# ColumnDriver.net
KiCad netlist of a schematic drawn in EAGLE
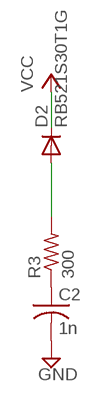
[diagram p0: schematic, sheet 1]

(export (version "E")
  (design (tool "Eeschema 10.0.6"))
  (components
    (comp (ref "C2")
      (value "1n")
      (footprint "eagle-import:C0805")
      (libsource (lib "eagle-import") (part "C-USC0805"))
    )
    (comp (ref "D2")
      (value "RB521S30T1G")
      (footprint "eagle-import:SOD523")
      (libsource (lib "eagle-import") (part "DIODE-SOD523"))
    )
    (comp (ref "R3")
      (value "300")
      (footprint "eagle-import:R0805")
      (libsource (lib "eagle-import") (part "R-US_R0805"))
    )
  )
  (nets
    (net (code "1") (name "GND") (class "Default")
      (node (ref "C2") (pin "2") (pinfunction "2_2") (pintype "passive"))
    )
    (net (code "2") (name "Net-(C2-Pad1)") (class "Default")
      (node (ref "C2") (pin "1") (pinfunction "1_1") (pintype "passive"))
      (node (ref "R3") (pin "1") (pinfunction "1_1") (pintype "passive"))
    )
    (net (code "3") (name "Net-(D2-PadA)") (class "Default")
      (node (ref "D2") (pin "A") (pinfunction "A_A") (pintype "passive"))
      (node (ref "R3") (pin "2") (pinfunction "2_2") (pintype "passive"))
    )
    (net (code "4") (name "VCC") (class "Default")
      (node (ref "D2") (pin "C") (pinfunction "C_C") (pintype "passive"))
    )
  )
)
